# MF.net
KiCad netlist of a schematic drawn in EAGLE
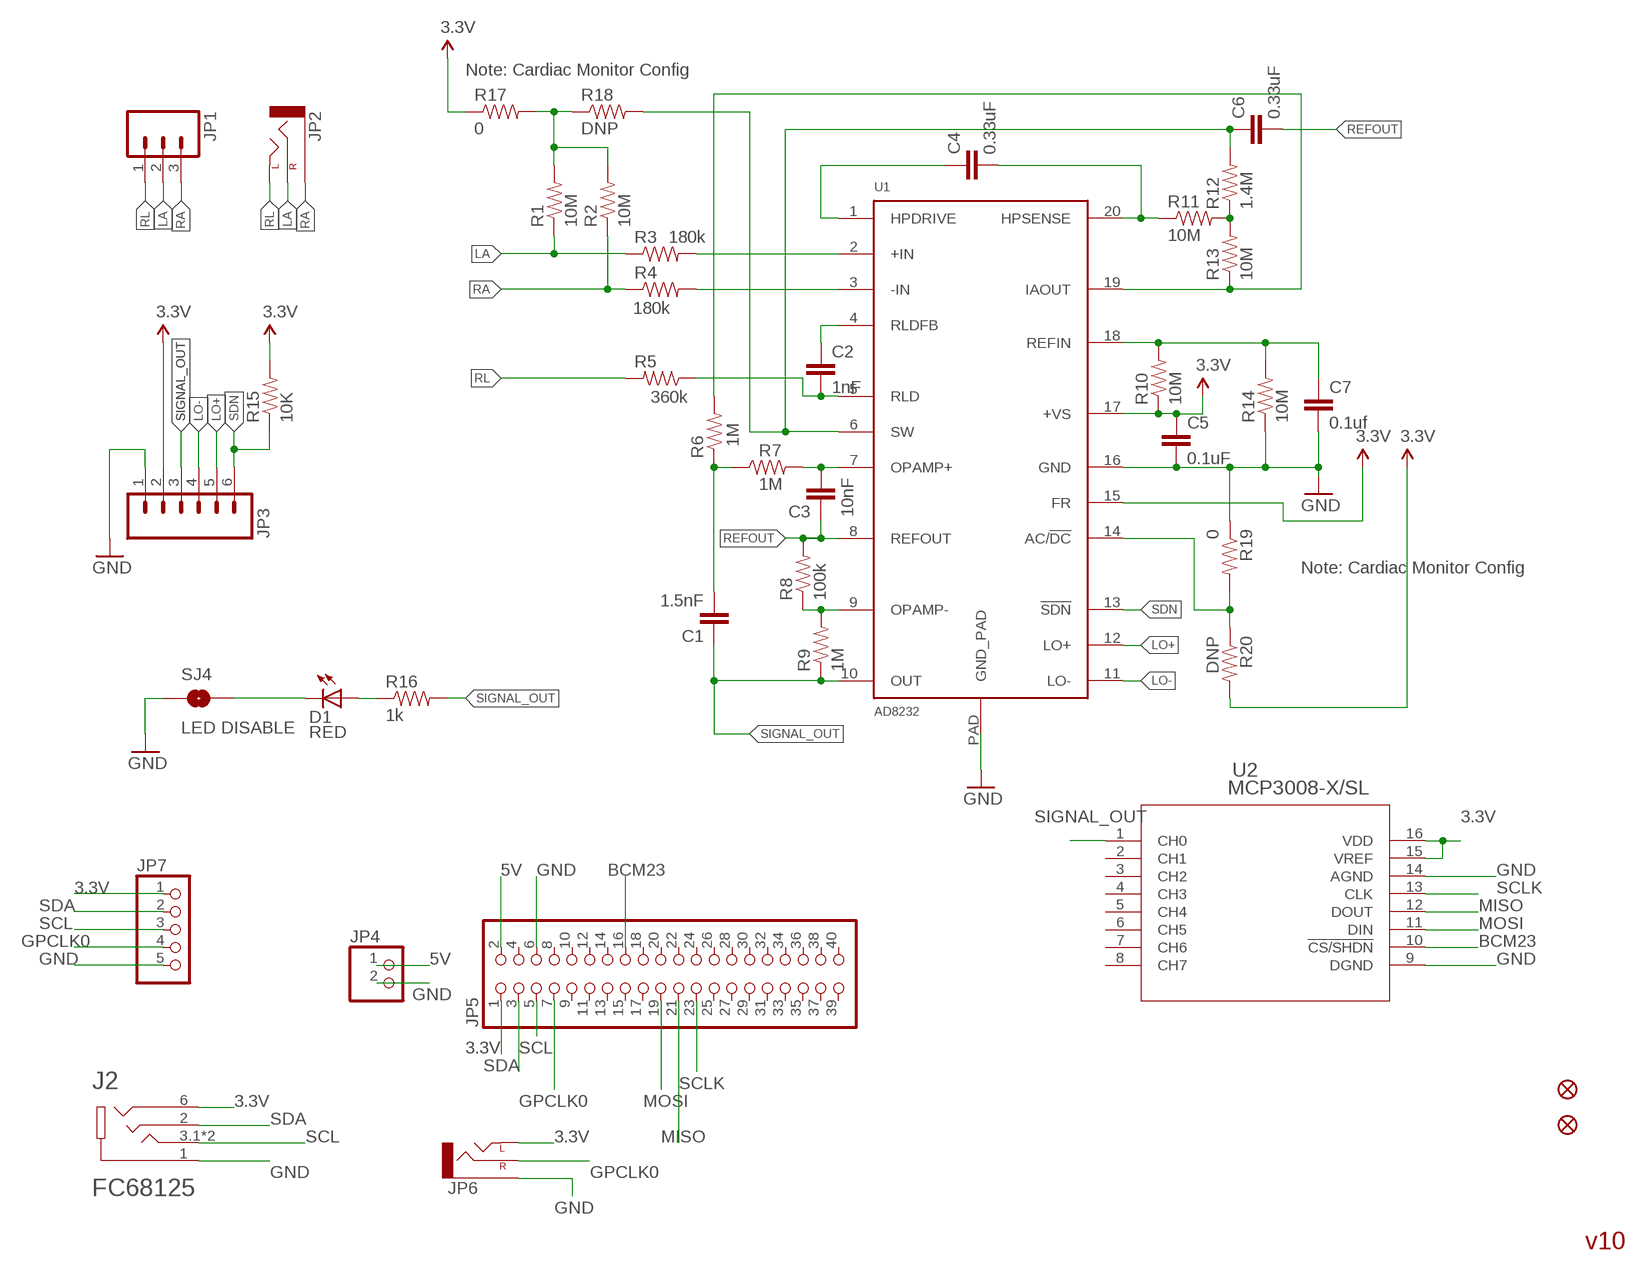
[diagram p0: schematic, sheet 1]

(export (version "E")
  (design (tool "Eeschema 10.0.6"))
  (components
    (comp (ref "C1")
      (value "1.5nF")
      (footprint "eagle-import:0603-CAP")
      (libsource (lib "eagle-import") (part "CAP0603-CAP"))
    )
    (comp (ref "C2")
      (value "1nF")
      (footprint "eagle-import:0603-CAP")
      (libsource (lib "eagle-import") (part "CAP0603-CAP"))
    )
    (comp (ref "C3")
      (value "10nF")
      (footprint "eagle-import:0603-CAP")
      (libsource (lib "eagle-import") (part "CAP0603-CAP"))
    )
    (comp (ref "C4")
      (value "0.33uF")
      (footprint "eagle-import:0805")
      (libsource (lib "eagle-import") (part "CAP0805"))
    )
    (comp (ref "C5")
      (value "0.1uF")
      (footprint "eagle-import:0603-CAP")
      (libsource (lib "eagle-import") (part "CAP0603-CAP"))
    )
    (comp (ref "C6")
      (value "0.33uF")
      (footprint "eagle-import:0805")
      (libsource (lib "eagle-import") (part "CAP0805"))
    )
    (comp (ref "C7")
      (value "0.1uf")
      (footprint "eagle-import:0603-CAP")
      (libsource (lib "eagle-import") (part "CAP0603-CAP"))
    )
    (comp (ref "D1")
      (value "RED")
      (footprint "eagle-import:LED-0603")
      (libsource (lib "eagle-import") (part "LED-RED0603"))
    )
    (comp (ref "FID1")
      (value "FIDUCIAL1X2")
      (footprint "eagle-import:FIDUCIAL-1X2")
      (libsource (lib "eagle-import") (part "FIDUCIAL1X2"))
    )
    (comp (ref "FID2")
      (value "FIDUCIAL1X2")
      (footprint "eagle-import:FIDUCIAL-1X2")
      (libsource (lib "eagle-import") (part "FIDUCIAL1X2"))
    )
    (comp (ref "J2")
      (value "FC68125")
      (footprint "eagle-import:CLIFF_FC68125")
      (fields (field (name "MF") "Cliff Electronics"))
      (libsource (lib "eagle-import") (part "FC68125"))
    )
    (comp (ref "JP1")
      (value "M03PTH")
      (footprint "eagle-import:1X03")
      (libsource (lib "eagle-import") (part "M03PTH"))
    )
    (comp (ref "JP2")
      (value "AUDIO-JACKSMD2")
      (footprint "eagle-import:AUDIO-JACK-3.5MM-SMD")
      (libsource (lib "eagle-import") (part "AUDIO-JACKSMD2"))
    )
    (comp (ref "JP3")
      (value "M06SIP")
      (footprint "eagle-import:1X06")
      (libsource (lib "eagle-import") (part "M06SIP"))
    )
    (comp (ref "JP4")
      (value "PINHD-1X2")
      (footprint "eagle-import:1X02")
      (libsource (lib "eagle-import") (part "PINHD-1X2"))
    )
    (comp (ref "JP5")
      (value "PINHD-2X20")
      (footprint "eagle-import:2X20")
      (libsource (lib "eagle-import") (part "PINHD-2X20"))
    )
    (comp (ref "JP6")
      (value "AUDIO-JACKSMD2")
      (footprint "eagle-import:AUDIO-JACK-3.5MM-SMD")
      (libsource (lib "eagle-import") (part "AUDIO-JACKSMD2"))
    )
    (comp (ref "JP7")
      (value "PINHD-1X5")
      (footprint "eagle-import:1X05")
      (libsource (lib "eagle-import") (part "PINHD-1X5"))
    )
    (comp (ref "R1")
      (value "10M")
      (footprint "eagle-import:0603-RES")
      (libsource (lib "eagle-import") (part "RESISTOR0603-RES"))
    )
    (comp (ref "R2")
      (value "10M")
      (footprint "eagle-import:0603-RES")
      (libsource (lib "eagle-import") (part "RESISTOR0603-RES"))
    )
    (comp (ref "R3")
      (value "180k")
      (footprint "eagle-import:0603-RES")
      (libsource (lib "eagle-import") (part "RESISTOR0603-RES"))
    )
    (comp (ref "R4")
      (value "180k")
      (footprint "eagle-import:0603-RES")
      (libsource (lib "eagle-import") (part "RESISTOR0603-RES"))
    )
    (comp (ref "R5")
      (value "360k")
      (footprint "eagle-import:0603-RES")
      (libsource (lib "eagle-import") (part "RESISTOR0603-RES"))
    )
    (comp (ref "R6")
      (value "1M")
      (footprint "eagle-import:0603-RES")
      (libsource (lib "eagle-import") (part "RESISTOR0603-RES"))
    )
    (comp (ref "R7")
      (value "1M")
      (footprint "eagle-import:0603-RES")
      (libsource (lib "eagle-import") (part "RESISTOR0603-RES"))
    )
    (comp (ref "R8")
      (value "100k")
      (footprint "eagle-import:0603-RES")
      (libsource (lib "eagle-import") (part "RESISTOR0603-RES"))
    )
    (comp (ref "R9")
      (value "1M")
      (footprint "eagle-import:0603-RES")
      (libsource (lib "eagle-import") (part "RESISTOR0603-RES"))
    )
    (comp (ref "R10")
      (value "10M")
      (footprint "eagle-import:0603-RES")
      (libsource (lib "eagle-import") (part "RESISTOR0603-RES"))
    )
    (comp (ref "R11")
      (value "10M")
      (footprint "eagle-import:0603-RES")
      (libsource (lib "eagle-import") (part "RESISTOR0603-RES"))
    )
    (comp (ref "R12")
      (value "1.4M")
      (footprint "eagle-import:0603-RES")
      (libsource (lib "eagle-import") (part "RESISTOR0603-RES"))
    )
    (comp (ref "R13")
      (value "10M")
      (footprint "eagle-import:0603-RES")
      (libsource (lib "eagle-import") (part "RESISTOR0603-RES"))
    )
    (comp (ref "R14")
      (value "10M")
      (footprint "eagle-import:0603-RES")
      (libsource (lib "eagle-import") (part "RESISTOR0603-RES"))
    )
    (comp (ref "R15")
      (value "10K")
      (footprint "eagle-import:0603-RES")
      (libsource (lib "eagle-import") (part "10KOHM1/10W1%(0603)0603"))
    )
    (comp (ref "R16")
      (value "1k")
      (footprint "eagle-import:0603-RES")
      (libsource (lib "eagle-import") (part "1K-1%"))
    )
    (comp (ref "R17")
      (value "0")
      (footprint "eagle-import:0603")
      (libsource (lib "eagle-import") (part "0OHM1/10W5%(0603)"))
    )
    (comp (ref "R18")
      (value "DNP")
      (footprint "eagle-import:0603")
      (libsource (lib "eagle-import") (part "0OHM1/10W5%(0603)"))
    )
    (comp (ref "R19")
      (value "0")
      (footprint "eagle-import:0603")
      (libsource (lib "eagle-import") (part "0OHM1/10W5%(0603)"))
    )
    (comp (ref "R20")
      (value "DNP")
      (footprint "eagle-import:0603")
      (libsource (lib "eagle-import") (part "0OHM1/10W5%(0603)"))
    )
    (comp (ref "SJ4")
      (value "LED DISABLE")
      (footprint "eagle-import:SJ_2S-TRACE")
      (libsource (lib "eagle-import") (part "SOLDERJUMPERTRACE"))
    )
    (comp (ref "U1")
      (value "AD8232")
      (footprint "eagle-import:LFCSP_20")
      (libsource (lib "eagle-import") (part "AD8232"))
    )
    (comp (ref "U2")
      (value "MCP3008-X/SL")
      (footprint "eagle-import:SOIC16-N_MC")
      (fields (field (name "MANUFACTURER_PART_NUMBER") "MCP3008XSL"))
      (libsource (lib "eagle-import") (part "MCP3008-X/SL"))
    )
  )
  (nets
    (net (code "1") (name "/5V") (class "Default")
      (node (ref "JP4") (pin "1") (pinfunction "1_1") (pintype "passive"))
      (node (ref "JP5") (pin "2") (pinfunction "2_2") (pintype "passive"))
    )
    (net (code "2") (name "/BCM23") (class "Default")
      (node (ref "JP5") (pin "16") (pinfunction "16_16") (pintype "passive"))
      (node (ref "U2") (pin "10") (pinfunction "~{CS/SHDN}_10") (pintype "passive"))
    )
    (net (code "3") (name "/GPCLK0") (class "Default")
      (node (ref "JP5") (pin "7") (pinfunction "7_7") (pintype "passive"))
      (node (ref "JP6") (pin "RING") (pinfunction "RIGHT_RING") (pintype "bidirectional"))
      (node (ref "JP7") (pin "4") (pinfunction "4_4") (pintype "passive"))
    )
    (net (code "4") (name "/MISO") (class "Default")
      (node (ref "JP5") (pin "21") (pinfunction "21_21") (pintype "passive"))
      (node (ref "U2") (pin "12") (pinfunction "DOUT_12") (pintype "passive"))
    )
    (net (code "5") (name "/MOSI") (class "Default")
      (node (ref "JP5") (pin "19") (pinfunction "19_19") (pintype "passive"))
      (node (ref "U2") (pin "11") (pinfunction "DIN_11") (pintype "passive"))
    )
    (net (code "6") (name "/SCL") (class "Default")
      (node (ref "J2") (pin "3.1") (pinfunction "3T_3.1") (pintype "passive"))
      (node (ref "J2") (pin "3.2") (pinfunction "3T_3.2") (pintype "passive"))
      (node (ref "JP5") (pin "5") (pinfunction "5_5") (pintype "passive"))
      (node (ref "JP7") (pin "3") (pinfunction "3_3") (pintype "passive"))
    )
    (net (code "7") (name "/SCLK") (class "Default")
      (node (ref "JP5") (pin "23") (pinfunction "23_23") (pintype "passive"))
      (node (ref "U2") (pin "13") (pinfunction "CLK_13") (pintype "passive"))
    )
    (net (code "8") (name "/SDA") (class "Default")
      (node (ref "J2") (pin "2") (pinfunction "2R_2") (pintype "passive"))
      (node (ref "JP5") (pin "3") (pinfunction "3_3") (pintype "passive"))
      (node (ref "JP7") (pin "2") (pinfunction "2_2") (pintype "passive"))
    )
    (net (code "9") (name "3.3V") (class "Default")
      (node (ref "C5") (pin "1") (pinfunction "1_1") (pintype "passive"))
      (node (ref "J2") (pin "6") (pinfunction "6SR_6") (pintype "passive"))
      (node (ref "JP3") (pin "2") (pinfunction "2_2") (pintype "passive"))
      (node (ref "JP5") (pin "1") (pinfunction "1_1") (pintype "passive"))
      (node (ref "JP6") (pin "TIP") (pinfunction "LEFT_TIP") (pintype "bidirectional"))
      (node (ref "JP7") (pin "1") (pinfunction "1_1") (pintype "passive"))
      (node (ref "R10") (pin "1") (pinfunction "1_1") (pintype "passive"))
      (node (ref "R15") (pin "2") (pinfunction "2_2") (pintype "passive"))
      (node (ref "R17") (pin "1") (pinfunction "1_1") (pintype "passive"))
      (node (ref "R20") (pin "2") (pinfunction "2_2") (pintype "passive"))
      (node (ref "U1") (pin "15") (pinfunction "FR_15") (pintype "bidirectional"))
      (node (ref "U1") (pin "17") (pinfunction "+VS_17") (pintype "bidirectional"))
      (node (ref "U2") (pin "15") (pinfunction "VREF_15") (pintype "passive"))
      (node (ref "U2") (pin "16") (pinfunction "VDD_16") (pintype "passive"))
    )
    (net (code "10") (name "GND") (class "Default")
      (node (ref "C5") (pin "2") (pinfunction "2_2") (pintype "passive"))
      (node (ref "C7") (pin "2") (pinfunction "2_2") (pintype "passive"))
      (node (ref "J2") (pin "1") (pinfunction "1S_1") (pintype "passive"))
      (node (ref "JP3") (pin "1") (pinfunction "1_1") (pintype "passive"))
      (node (ref "JP4") (pin "2") (pinfunction "2_2") (pintype "passive"))
      (node (ref "JP5") (pin "6") (pinfunction "6_6") (pintype "passive"))
      (node (ref "JP6") (pin "SLEEVE") (pinfunction "SLEEVE_SLEEVE") (pintype "bidirectional"))
      (node (ref "JP7") (pin "5") (pinfunction "5_5") (pintype "passive"))
      (node (ref "R14") (pin "1") (pinfunction "1_1") (pintype "passive"))
      (node (ref "R19") (pin "1") (pinfunction "1_1") (pintype "passive"))
      (node (ref "SJ4") (pin "1") (pinfunction "1_1") (pintype "passive"))
      (node (ref "U1") (pin "16") (pinfunction "GND_16") (pintype "bidirectional"))
      (node (ref "U1") (pin "PAD") (pinfunction "GND_PAD_PAD") (pintype "bidirectional"))
      (node (ref "U2") (pin "14") (pinfunction "AGND_14") (pintype "passive"))
      (node (ref "U2") (pin "9") (pinfunction "DGND_9") (pintype "passive"))
    )
    (net (code "11") (name "LA") (class "Default")
      (node (ref "JP1") (pin "2") (pinfunction "2_2") (pintype "passive"))
      (node (ref "JP2") (pin "RING") (pinfunction "RIGHT_RING") (pintype "bidirectional"))
      (node (ref "R1") (pin "1") (pinfunction "1_1") (pintype "passive"))
      (node (ref "R3") (pin "1") (pinfunction "1_1") (pintype "passive"))
    )
    (net (code "12") (name "LO+") (class "Default")
      (node (ref "JP3") (pin "5") (pinfunction "5_5") (pintype "passive"))
      (node (ref "U1") (pin "12") (pinfunction "LO+_12") (pintype "bidirectional"))
    )
    (net (code "13") (name "LO-") (class "Default")
      (node (ref "JP3") (pin "4") (pinfunction "4_4") (pintype "passive"))
      (node (ref "U1") (pin "11") (pinfunction "LO-_11") (pintype "bidirectional"))
    )
    (net (code "14") (name "Net-(C1-Pad2)") (class "Default")
      (node (ref "C1") (pin "2") (pinfunction "2_2") (pintype "passive"))
      (node (ref "R6") (pin "1") (pinfunction "1_1") (pintype "passive"))
      (node (ref "R7") (pin "1") (pinfunction "1_1") (pintype "passive"))
    )
    (net (code "15") (name "Net-(D1-PadA)") (class "Default")
      (node (ref "D1") (pin "A") (pinfunction "A_A") (pintype "passive"))
      (node (ref "R16") (pin "1") (pinfunction "1_1") (pintype "passive"))
    )
    (net (code "16") (name "Net-(D1-PadC)") (class "Default")
      (node (ref "D1") (pin "C") (pinfunction "C_C") (pintype "passive"))
      (node (ref "SJ4") (pin "2") (pinfunction "2_2") (pintype "passive"))
    )
    (net (code "17") (name "Net-(R1-Pad2)") (class "Default")
      (node (ref "R1") (pin "2") (pinfunction "2_2") (pintype "passive"))
      (node (ref "R17") (pin "2") (pinfunction "2_2") (pintype "passive"))
      (node (ref "R18") (pin "1") (pinfunction "1_1") (pintype "passive"))
      (node (ref "R2") (pin "2") (pinfunction "2_2") (pintype "passive"))
    )
    (net (code "18") (name "Net-(R11-Pad2)") (class "Default")
      (node (ref "R11") (pin "2") (pinfunction "2_2") (pintype "passive"))
      (node (ref "R12") (pin "1") (pinfunction "1_1") (pintype "passive"))
      (node (ref "R13") (pin "2") (pinfunction "2_2") (pintype "passive"))
    )
    (net (code "19") (name "Net-(U1-+IN)") (class "Default")
      (node (ref "R3") (pin "2") (pinfunction "2_2") (pintype "passive"))
      (node (ref "U1") (pin "2") (pinfunction "+IN_2") (pintype "bidirectional"))
    )
    (net (code "20") (name "Net-(U1--IN)") (class "Default")
      (node (ref "R4") (pin "2") (pinfunction "2_2") (pintype "passive"))
      (node (ref "U1") (pin "3") (pinfunction "-IN_3") (pintype "bidirectional"))
    )
    (net (code "21") (name "Net-(U1-AC{slash}~{DC})") (class "Default")
      (node (ref "R19") (pin "2") (pinfunction "2_2") (pintype "passive"))
      (node (ref "R20") (pin "1") (pinfunction "1_1") (pintype "passive"))
      (node (ref "U1") (pin "14") (pinfunction "AC/~{DC}_14") (pintype "bidirectional"))
    )
    (net (code "22") (name "Net-(U1-HPDRIVE)") (class "Default")
      (node (ref "C4") (pin "1") (pinfunction "1_1") (pintype "passive"))
      (node (ref "U1") (pin "1") (pinfunction "HPDRIVE_1") (pintype "bidirectional"))
    )
    (net (code "23") (name "Net-(U1-HPSENSE)") (class "Default")
      (node (ref "C4") (pin "2") (pinfunction "2_2") (pintype "passive"))
      (node (ref "R11") (pin "1") (pinfunction "1_1") (pintype "passive"))
      (node (ref "U1") (pin "20") (pinfunction "HPSENSE_20") (pintype "bidirectional"))
    )
    (net (code "24") (name "Net-(U1-IAOUT)") (class "Default")
      (node (ref "R13") (pin "1") (pinfunction "1_1") (pintype "passive"))
      (node (ref "R6") (pin "2") (pinfunction "2_2") (pintype "passive"))
      (node (ref "U1") (pin "19") (pinfunction "IAOUT_19") (pintype "bidirectional"))
    )
    (net (code "25") (name "Net-(U1-OPAMP+)") (class "Default")
      (node (ref "C3") (pin "2") (pinfunction "2_2") (pintype "passive"))
      (node (ref "R7") (pin "2") (pinfunction "2_2") (pintype "passive"))
      (node (ref "U1") (pin "7") (pinfunction "OPAMP+_7") (pintype "bidirectional"))
    )
    (net (code "26") (name "Net-(U1-OPAMP-)") (class "Default")
      (node (ref "R8") (pin "1") (pinfunction "1_1") (pintype "passive"))
      (node (ref "R9") (pin "2") (pinfunction "2_2") (pintype "passive"))
      (node (ref "U1") (pin "9") (pinfunction "OPAMP-_9") (pintype "bidirectional"))
    )
    (net (code "27") (name "Net-(U1-REFIN)") (class "Default")
      (node (ref "C7") (pin "1") (pinfunction "1_1") (pintype "passive"))
      (node (ref "R10") (pin "2") (pinfunction "2_2") (pintype "passive"))
      (node (ref "R14") (pin "2") (pinfunction "2_2") (pintype "passive"))
      (node (ref "U1") (pin "18") (pinfunction "REFIN_18") (pintype "bidirectional"))
    )
    (net (code "28") (name "Net-(U1-RLD)") (class "Default")
      (node (ref "C2") (pin "2") (pinfunction "2_2") (pintype "passive"))
      (node (ref "R5") (pin "1") (pinfunction "1_1") (pintype "passive"))
      (node (ref "U1") (pin "5") (pinfunction "RLD_5") (pintype "bidirectional"))
    )
    (net (code "29") (name "Net-(U1-RLDFB)") (class "Default")
      (node (ref "C2") (pin "1") (pinfunction "1_1") (pintype "passive"))
      (node (ref "U1") (pin "4") (pinfunction "RLDFB_4") (pintype "bidirectional"))
    )
    (net (code "30") (name "Net-(U1-SW)") (class "Default")
      (node (ref "C6") (pin "1") (pinfunction "1_1") (pintype "passive"))
      (node (ref "R12") (pin "2") (pinfunction "2_2") (pintype "passive"))
      (node (ref "R18") (pin "2") (pinfunction "2_2") (pintype "passive"))
      (node (ref "U1") (pin "6") (pinfunction "SW_6") (pintype "bidirectional"))
    )
    (net (code "31") (name "RA") (class "Default")
      (node (ref "JP1") (pin "3") (pinfunction "3_3") (pintype "passive"))
      (node (ref "JP2") (pin "SLEEVE") (pinfunction "SLEEVE_SLEEVE") (pintype "bidirectional"))
      (node (ref "R2") (pin "1") (pinfunction "1_1") (pintype "passive"))
      (node (ref "R4") (pin "1") (pinfunction "1_1") (pintype "passive"))
    )
    (net (code "32") (name "REFOUT") (class "Default")
      (node (ref "C3") (pin "1") (pinfunction "1_1") (pintype "passive"))
      (node (ref "C6") (pin "2") (pinfunction "2_2") (pintype "passive"))
      (node (ref "R8") (pin "2") (pinfunction "2_2") (pintype "passive"))
      (node (ref "U1") (pin "8") (pinfunction "REFOUT_8") (pintype "bidirectional"))
    )
    (net (code "33") (name "RL") (class "Default")
      (node (ref "JP1") (pin "1") (pinfunction "1_1") (pintype "passive"))
      (node (ref "JP2") (pin "TIP") (pinfunction "LEFT_TIP") (pintype "bidirectional"))
      (node (ref "R5") (pin "2") (pinfunction "2_2") (pintype "passive"))
    )
    (net (code "34") (name "SDN") (class "Default")
      (node (ref "JP3") (pin "6") (pinfunction "6_6") (pintype "passive"))
      (node (ref "R15") (pin "1") (pinfunction "1_1") (pintype "passive"))
      (node (ref "U1") (pin "13") (pinfunction "~{SDN}_13") (pintype "bidirectional"))
    )
    (net (code "35") (name "SIGNAL_OUT") (class "Default")
      (node (ref "C1") (pin "1") (pinfunction "1_1") (pintype "passive"))
      (node (ref "JP3") (pin "3") (pinfunction "3_3") (pintype "passive"))
      (node (ref "R16") (pin "2") (pinfunction "2_2") (pintype "passive"))
      (node (ref "R9") (pin "1") (pinfunction "1_1") (pintype "passive"))
      (node (ref "U1") (pin "10") (pinfunction "OUT_10") (pintype "bidirectional"))
      (node (ref "U2") (pin "1") (pinfunction "CH0_1") (pintype "passive"))
    )
    (net (code "36") (name "unconnected-(JP5-Pad4)") (class "Default")
      (node (ref "JP5") (pin "4") (pinfunction "4_4") (pintype "passive"))
    )
    (net (code "37") (name "unconnected-(JP5-Pad8)") (class "Default")
      (node (ref "JP5") (pin "8") (pinfunction "8_8") (pintype "passive"))
    )
    (net (code "38") (name "unconnected-(JP5-Pad9)") (class "Default")
      (node (ref "JP5") (pin "9") (pinfunction "9_9") (pintype "passive"))
    )
    (net (code "39") (name "unconnected-(JP5-Pad10)") (class "Default")
      (node (ref "JP5") (pin "10") (pinfunction "10_10") (pintype "passive"))
    )
    (net (code "40") (name "unconnected-(JP5-Pad11)") (class "Default")
      (node (ref "JP5") (pin "11") (pinfunction "11_11") (pintype "passive"))
    )
    (net (code "41") (name "unconnected-(JP5-Pad12)") (class "Default")
      (node (ref "JP5") (pin "12") (pinfunction "12_12") (pintype "passive"))
    )
    (net (code "42") (name "unconnected-(JP5-Pad13)") (class "Default")
      (node (ref "JP5") (pin "13") (pinfunction "13_13") (pintype "passive"))
    )
    (net (code "43") (name "unconnected-(JP5-Pad14)") (class "Default")
      (node (ref "JP5") (pin "14") (pinfunction "14_14") (pintype "passive"))
    )
    (net (code "44") (name "unconnected-(JP5-Pad15)") (class "Default")
      (node (ref "JP5") (pin "15") (pinfunction "15_15") (pintype "passive"))
    )
    (net (code "45") (name "unconnected-(JP5-Pad17)") (class "Default")
      (node (ref "JP5") (pin "17") (pinfunction "17_17") (pintype "passive"))
    )
    (net (code "46") (name "unconnected-(JP5-Pad18)") (class "Default")
      (node (ref "JP5") (pin "18") (pinfunction "18_18") (pintype "passive"))
    )
    (net (code "47") (name "unconnected-(JP5-Pad20)") (class "Default")
      (node (ref "JP5") (pin "20") (pinfunction "20_20") (pintype "passive"))
    )
    (net (code "48") (name "unconnected-(JP5-Pad22)") (class "Default")
      (node (ref "JP5") (pin "22") (pinfunction "22_22") (pintype "passive"))
    )
    (net (code "49") (name "unconnected-(JP5-Pad24)") (class "Default")
      (node (ref "JP5") (pin "24") (pinfunction "24_24") (pintype "passive"))
    )
    (net (code "50") (name "unconnected-(JP5-Pad25)") (class "Default")
      (node (ref "JP5") (pin "25") (pinfunction "25_25") (pintype "passive"))
    )
    (net (code "51") (name "unconnected-(JP5-Pad26)") (class "Default")
      (node (ref "JP5") (pin "26") (pinfunction "26_26") (pintype "passive"))
    )
    (net (code "52") (name "unconnected-(JP5-Pad27)") (class "Default")
      (node (ref "JP5") (pin "27") (pinfunction "27_27") (pintype "passive"))
    )
    (net (code "53") (name "unconnected-(JP5-Pad28)") (class "Default")
      (node (ref "JP5") (pin "28") (pinfunction "28_28") (pintype "passive"))
    )
    (net (code "54") (name "unconnected-(JP5-Pad29)") (class "Default")
      (node (ref "JP5") (pin "29") (pinfunction "29_29") (pintype "passive"))
    )
    (net (code "55") (name "unconnected-(JP5-Pad30)") (class "Default")
      (node (ref "JP5") (pin "30") (pinfunction "30_30") (pintype "passive"))
    )
    (net (code "56") (name "unconnected-(JP5-Pad31)") (class "Default")
      (node (ref "JP5") (pin "31") (pinfunction "31_31") (pintype "passive"))
    )
    (net (code "57") (name "unconnected-(JP5-Pad32)") (class "Default")
      (node (ref "JP5") (pin "32") (pinfunction "32_32") (pintype "passive"))
    )
    (net (code "58") (name "unconnected-(JP5-Pad33)") (class "Default")
      (node (ref "JP5") (pin "33") (pinfunction "33_33") (pintype "passive"))
    )
    (net (code "59") (name "unconnected-(JP5-Pad34)") (class "Default")
      (node (ref "JP5") (pin "34") (pinfunction "34_34") (pintype "passive"))
    )
    (net (code "60") (name "unconnected-(JP5-Pad35)") (class "Default")
      (node (ref "JP5") (pin "35") (pinfunction "35_35") (pintype "passive"))
    )
    (net (code "61") (name "unconnected-(JP5-Pad36)") (class "Default")
      (node (ref "JP5") (pin "36") (pinfunction "36_36") (pintype "passive"))
    )
    (net (code "62") (name "unconnected-(JP5-Pad37)") (class "Default")
      (node (ref "JP5") (pin "37") (pinfunction "37_37") (pintype "passive"))
    )
    (net (code "63") (name "unconnected-(JP5-Pad38)") (class "Default")
      (node (ref "JP5") (pin "38") (pinfunction "38_38") (pintype "passive"))
    )
    (net (code "64") (name "unconnected-(JP5-Pad39)") (class "Default")
      (node (ref "JP5") (pin "39") (pinfunction "39_39") (pintype "passive"))
    )
    (net (code "65") (name "unconnected-(JP5-Pad40)") (class "Default")
      (node (ref "JP5") (pin "40") (pinfunction "40_40") (pintype "passive"))
    )
    (net (code "66") (name "unconnected-(U2-CH1-Pad2)") (class "Default")
      (node (ref "U2") (pin "2") (pinfunction "CH1_2") (pintype "passive"))
    )
    (net (code "67") (name "unconnected-(U2-CH2-Pad3)") (class "Default")
      (node (ref "U2") (pin "3") (pinfunction "CH2_3") (pintype "passive"))
    )
    (net (code "68") (name "unconnected-(U2-CH3-Pad4)") (class "Default")
      (node (ref "U2") (pin "4") (pinfunction "CH3_4") (pintype "passive"))
    )
    (net (code "69") (name "unconnected-(U2-CH4-Pad5)") (class "Default")
      (node (ref "U2") (pin "5") (pinfunction "CH4_5") (pintype "passive"))
    )
    (net (code "70") (name "unconnected-(U2-CH5-Pad6)") (class "Default")
      (node (ref "U2") (pin "6") (pinfunction "CH5_6") (pintype "passive"))
    )
    (net (code "71") (name "unconnected-(U2-CH6-Pad7)") (class "Default")
      (node (ref "U2") (pin "7") (pinfunction "CH6_7") (pintype "passive"))
    )
    (net (code "72") (name "unconnected-(U2-CH7-Pad8)") (class "Default")
      (node (ref "U2") (pin "8") (pinfunction "CH7_8") (pintype "passive"))
    )
  )
)
